# Test_Jig_BMP2.net
KiCad netlist of a schematic drawn in Altium Designer
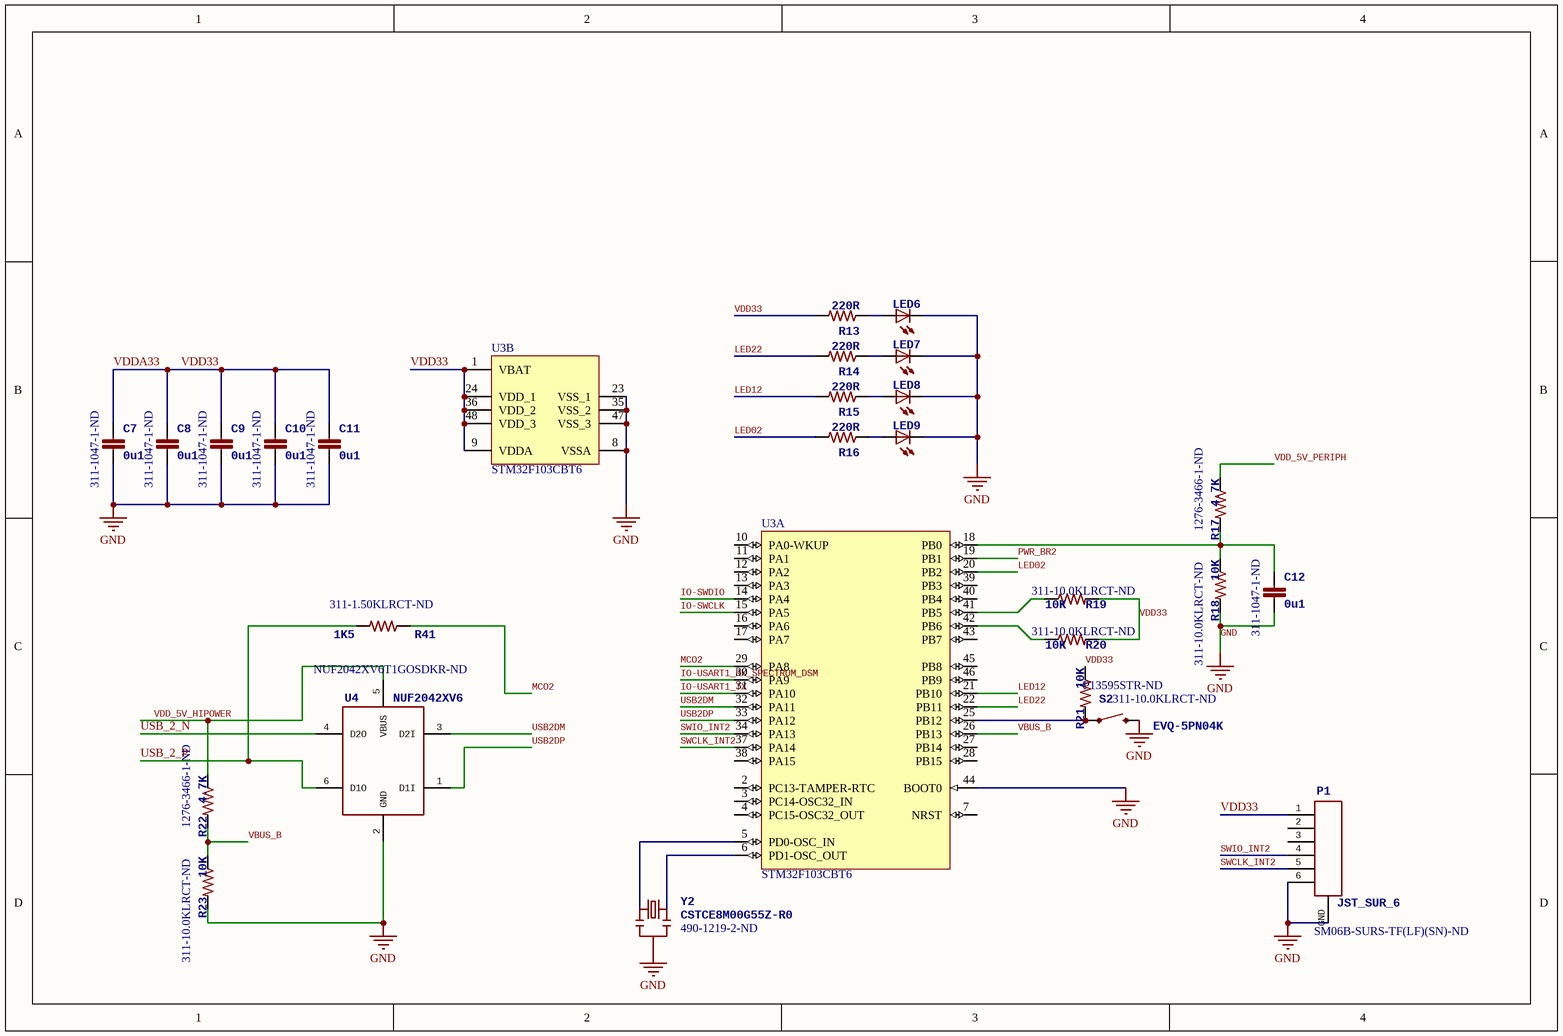
[diagram p0: Test_Jig_BMP2.SchDoc]

(export (version "E")
  (design (tool "Eeschema 10.0.6"))
  (components
    (comp (ref "C7")
      (value "0u1")
      (footprint "0402-CAP")
      (description "CAP CER 0.1UF 16V Y5V 0402")
      (fields
        (field (name "PARTNO") "CC0402ZRY5V7BB104")
        (field (name "SUPPLIER PART NUMBER 1") "311-1047-1-ND")
        (field (name "3DR_PARTNO") "ECM0700")
      )
      (libsource (lib "pixhawk2") (part "CAP0402"))
    )
    (comp (ref "C8")
      (value "0u1")
      (footprint "0402-CAP")
      (description "CAP CER 0.1UF 16V Y5V 0402")
      (fields
        (field (name "PARTNO") "CC0402ZRY5V7BB104")
        (field (name "SUPPLIER PART NUMBER 1") "311-1047-1-ND")
        (field (name "3DR_PARTNO") "ECM0700")
      )
      (libsource (lib "pixhawk2") (part "CAP0402"))
    )
    (comp (ref "C9")
      (value "0u1")
      (footprint "0402-CAP")
      (description "CAP CER 0.1UF 16V Y5V 0402")
      (fields
        (field (name "PARTNO") "CC0402ZRY5V7BB104")
        (field (name "SUPPLIER PART NUMBER 1") "311-1047-1-ND")
        (field (name "3DR_PARTNO") "ECM0700")
      )
      (libsource (lib "pixhawk2") (part "CAP0402"))
    )
    (comp (ref "C10")
      (value "0u1")
      (footprint "0402-CAP")
      (description "CAP CER 0.1UF 16V Y5V 0402")
      (fields
        (field (name "PARTNO") "CC0402ZRY5V7BB104")
        (field (name "SUPPLIER PART NUMBER 1") "311-1047-1-ND")
        (field (name "3DR_PARTNO") "ECM0700")
      )
      (libsource (lib "pixhawk2") (part "CAP0402"))
    )
    (comp (ref "C11")
      (value "0u1")
      (footprint "0402-CAP")
      (description "CAP CER 0.1UF 16V Y5V 0402")
      (fields
        (field (name "PARTNO") "CC0402ZRY5V7BB104")
        (field (name "SUPPLIER PART NUMBER 1") "311-1047-1-ND")
        (field (name "3DR_PARTNO") "ECM0700")
      )
      (libsource (lib "pixhawk2") (part "CAP0402"))
    )
    (comp (ref "C12")
      (value "0u1")
      (footprint "0402-CAP")
      (description "CAP CER 0.1UF 16V Y5V 0402")
      (fields
        (field (name "PARTNO") "CC0402ZRY5V7BB104")
        (field (name "SUPPLIER PART NUMBER 1") "311-1047-1-ND")
        (field (name "3DR_PARTNO") "ECM0700")
      )
      (libsource (lib "pixhawk2") (part "CAP0402"))
    )
    (comp (ref "LED6")
      (value "LED0603_Green")
      (footprint "0603-LED-Blue")
      (description "LED GREEN ROUND CLEAR SMD")
      (fields (field (name "3DR_PARTNO") "ECM0494") (field (name "PARTNO") "APTD1608CGCK"))
      (libsource (lib "pixhawk2") (part "LED0603_Blue"))
    )
    (comp (ref "LED7")
      (value "LED0603_Green")
      (footprint "0603-LED-Blue")
      (description "LED GREEN ROUND CLEAR SMD")
      (fields (field (name "3DR_PARTNO") "ECM0494") (field (name "PARTNO") "APTD1608CGCK"))
      (libsource (lib "pixhawk2") (part "LED0603_Blue"))
    )
    (comp (ref "LED8")
      (value "LED0603_Green")
      (footprint "0603-LED-Blue")
      (description "LED GREEN ROUND CLEAR SMD")
      (fields (field (name "3DR_PARTNO") "ECM0494") (field (name "PARTNO") "APTD1608CGCK"))
      (libsource (lib "pixhawk2") (part "LED0603_Blue"))
    )
    (comp (ref "LED9")
      (value "LED0603_Green")
      (footprint "0603-LED-Blue")
      (description "LED GREEN ROUND CLEAR SMD")
      (fields (field (name "3DR_PARTNO") "ECM0494") (field (name "PARTNO") "APTD1608CGCK"))
      (libsource (lib "pixhawk2") (part "LED0603_Blue"))
    )
    (comp (ref "P1")
      (value "JST_SUR_6")
      (footprint "JST_SUR_H6")
      (description "Connector, Header, 6Pos, .8mm IDC, R/A, SMD, Tin")
      (fields
        (field (name "SUPPLIER PART NUMBER 1") "SM06B-SURS-TF(LF)(SN)-ND")
        (field (name "3DR_PARTNO") "PRT0442")
      )
      (libsource (lib "PCA_0005_FULL_CB_REV_A") (part "JST_SUR_6"))
    )
    (comp (ref "R13")
      (value "220R")
      (footprint "0402-RES")
      (description "RES 220 OHM 1/16W 1% 0402 SMD")
      (fields (field (name "PARTNO") "RC0402FR-07220RL") (field (name "3DR_PARTNO") "ECM0821"))
      (libsource (lib "pixhawk2") (part "RESISTOR0402-RES"))
    )
    (comp (ref "R14")
      (value "220R")
      (footprint "0402-RES")
      (description "RES 220 OHM 1/16W 1% 0402 SMD")
      (fields (field (name "PARTNO") "RC0402FR-07220RL") (field (name "3DR_PARTNO") "ECM0821"))
      (libsource (lib "pixhawk2") (part "RESISTOR0402-RES"))
    )
    (comp (ref "R15")
      (value "220R")
      (footprint "0402-RES")
      (description "RES 220 OHM 1/16W 1% 0402 SMD")
      (fields (field (name "PARTNO") "RC0402FR-07220RL") (field (name "3DR_PARTNO") "ECM0821"))
      (libsource (lib "pixhawk2") (part "RESISTOR0402-RES"))
    )
    (comp (ref "R16")
      (value "220R")
      (footprint "0402-RES")
      (description "RES 220 OHM 1/16W 1% 0402 SMD")
      (fields (field (name "PARTNO") "RC0402FR-07220RL") (field (name "3DR_PARTNO") "ECM0821"))
      (libsource (lib "pixhawk2") (part "RESISTOR0402-RES"))
    )
    (comp (ref "R17")
      (value "4.7K")
      (footprint "0402-RES")
      (description "RES 10K OHM 1/16W 1% 0402 SMD")
      (fields (field (name "PARTNO") "RC1005F472CS") (field (name "SUPPLIER PART NUMBER 1") "1276-3466-1-ND"))
      (libsource (lib "pixhawk2") (part "RESISTOR0402-RES"))
    )
    (comp (ref "R18")
      (value "10K")
      (footprint "0402-RES")
      (description "RES 10K OHM 1/16W 1% 0402 SMD")
      (fields
        (field (name "PARTNO") "RC0402FR-0710KL")
        (field (name "SUPPLIER PART NUMBER 1") "311-10.0KLRCT-ND")
        (field (name "3DR_PARTNO") "ECM0800")
      )
      (libsource (lib "pixhawk2") (part "RESISTOR0402-RES"))
    )
    (comp (ref "R19")
      (value "10K")
      (footprint "0402-RES")
      (description "RES 10K OHM 1/16W 1% 0402 SMD")
      (fields
        (field (name "PARTNO") "RC0402FR-0710KL")
        (field (name "SUPPLIER PART NUMBER 1") "311-10.0KLRCT-ND")
        (field (name "3DR_PARTNO") "ECM0800")
      )
      (libsource (lib "pixhawk2") (part "RESISTOR0402-RES"))
    )
    (comp (ref "R20")
      (value "10K")
      (footprint "0402-RES")
      (description "RES 10K OHM 1/16W 1% 0402 SMD")
      (fields
        (field (name "PARTNO") "RC0402FR-0710KL")
        (field (name "SUPPLIER PART NUMBER 1") "311-10.0KLRCT-ND")
        (field (name "3DR_PARTNO") "ECM0800")
      )
      (libsource (lib "pixhawk2") (part "RESISTOR0402-RES"))
    )
    (comp (ref "R21")
      (value "10K")
      (footprint "0402-RES")
      (description "RES 10K OHM 1/16W 1% 0402 SMD")
      (fields
        (field (name "PARTNO") "RC0402FR-0710KL")
        (field (name "SUPPLIER PART NUMBER 1") "311-10.0KLRCT-ND")
        (field (name "3DR_PARTNO") "ECM0800")
      )
      (libsource (lib "pixhawk2") (part "RESISTOR0402-RES"))
    )
    (comp (ref "R22")
      (value "4.7K")
      (footprint "0402-RES")
      (description "RES 10K OHM 1/16W 1% 0402 SMD")
      (fields (field (name "PARTNO") "RC1005F472CS") (field (name "SUPPLIER PART NUMBER 1") "1276-3466-1-ND"))
      (libsource (lib "pixhawk2") (part "RESISTOR0402-RES"))
    )
    (comp (ref "R23")
      (value "10K")
      (footprint "0402-RES")
      (description "RES 10K OHM 1/16W 1% 0402 SMD")
      (fields
        (field (name "PARTNO") "RC0402FR-0710KL")
        (field (name "SUPPLIER PART NUMBER 1") "311-10.0KLRCT-ND")
        (field (name "3DR_PARTNO") "ECM0800")
      )
      (libsource (lib "pixhawk2") (part "RESISTOR0402-RES"))
    )
    (comp (ref "R41")
      (value "1K5")
      (footprint "0402-RES")
      (description "RES 1.5K OHM 1/16W 1% 0402 SMD")
      (fields
        (field (name "PARTNO") "RC0402FR-071K5L")
        (field (name "SUPPLIER PART NUMBER 1") "311-1.50KLRCT-ND")
        (field (name "3DR_PARTNO") "ECM0803")
      )
      (libsource (lib "pixhawk2") (part "RESISTOR0402-RES"))
    )
    (comp (ref "S2")
      (value "EVQ-5PN04K")
      (footprint "TACTILE-SWITCH-1101NE")
      (fields (field (name "SUPPLIER PART NUMBER 1") "P13595STR-ND"))
      (libsource (lib "pixhawk2") (part "SWITCH-MOMENTARY-2-SMD-1101NE"))
    )
    (comp (ref "U3")
      (value "STM32F103CBT6")
      (footprint "STM-LQFP48_N")
      (libsource (lib "STMicroelectronics STM32 F1") (part "STM32F103CBT6"))
    )
    (comp (ref "U4")
      (value "NUF2042XV6")
      (footprint "SOT563-6")
      (description "IC FILTER USB ESD PROTECT SOT363")
      (fields
        (field (name "PARTNO") "NUF2042XV6T1G")
        (field (name "SUPPLIER PART NUMBER 1") "NUF2042XV6T1GOSDKR-ND")
        (field (name "3DR_PARTNO") "ECM0836")
      )
      (libsource (lib "pixhawk2") (part "NUF2042XV6"))
    )
    (comp (ref "Y2")
      (value "CSTCE8M00G55Z-R0")
      (footprint "RESONATOR-SMD")
      (fields (field (name "SUPPLIER PART NUMBER 1") "490-1219-2-ND"))
      (libsource (lib "SparkFun") (part "RESONATORSMD"))
    )
  )
  (nets
    (net (code "1") (name "/IO-SWCLK") (class "Default")
      (node (ref "U3") (pin "15") (pinfunction "PA5_15") (pintype "bidirectional"))
    )
    (net (code "2") (name "/IO-SWDIO") (class "Default")
      (node (ref "U3") (pin "14") (pinfunction "PA4_14") (pintype "bidirectional"))
    )
    (net (code "3") (name "/IO-USART1_RX_SPECTRUM_DSM") (class "Default")
      (node (ref "U3") (pin "30") (pinfunction "PA9_30") (pintype "bidirectional"))
    )
    (net (code "4") (name "/IO-USART1_TX") (class "Default")
      (node (ref "U3") (pin "31") (pinfunction "PA10_31") (pintype "bidirectional"))
    )
    (net (code "5") (name "/LED02") (class "Default")
      (node (ref "R16") (pin "P$2") (pinfunction "2_P$2") (pintype "passive"))
      (node (ref "U3") (pin "20") (pinfunction "PB2_20") (pintype "bidirectional"))
    )
    (net (code "6") (name "/LED12") (class "Default")
      (node (ref "R15") (pin "P$2") (pinfunction "2_P$2") (pintype "passive"))
      (node (ref "U3") (pin "21") (pinfunction "PB10_21") (pintype "bidirectional"))
    )
    (net (code "7") (name "/LED22") (class "Default")
      (node (ref "R14") (pin "P$2") (pinfunction "2_P$2") (pintype "passive"))
      (node (ref "U3") (pin "22") (pinfunction "PB11_22") (pintype "bidirectional"))
    )
    (net (code "8") (name "/MCO2") (class "Default")
      (node (ref "R41") (pin "P$1") (pinfunction "1_P$1") (pintype "passive"))
      (node (ref "U3") (pin "29") (pinfunction "PA8_29") (pintype "bidirectional"))
    )
    (net (code "9") (name "/PWR_BR2") (class "Default")
      (node (ref "U3") (pin "19") (pinfunction "PB1_19") (pintype "bidirectional"))
    )
    (net (code "10") (name "/SWCLK_INT2") (class "Default")
      (node (ref "P1") (pin "5") (pinfunction "5_5") (pintype "passive"))
      (node (ref "U3") (pin "37") (pinfunction "PA14_37") (pintype "bidirectional"))
    )
    (net (code "11") (name "/SWIO_INT2") (class "Default")
      (node (ref "P1") (pin "4") (pinfunction "4_4") (pintype "passive"))
      (node (ref "U3") (pin "34") (pinfunction "PA13_34") (pintype "bidirectional"))
    )
    (net (code "12") (name "/USB2DM") (class "Default")
      (node (ref "U3") (pin "32") (pinfunction "PA11_32") (pintype "bidirectional"))
      (node (ref "U4") (pin "3") (pinfunction "D2I_3") (pintype "passive"))
    )
    (net (code "13") (name "/USB2DP") (class "Default")
      (node (ref "U3") (pin "33") (pinfunction "PA12_33") (pintype "bidirectional"))
      (node (ref "U4") (pin "1") (pinfunction "D1I_1") (pintype "passive"))
    )
    (net (code "14") (name "/USB_2_N") (class "Default")
      (node (ref "U4") (pin "4") (pinfunction "D2O_4") (pintype "passive"))
    )
    (net (code "15") (name "/USB_2_P") (class "Default")
      (node (ref "R41") (pin "P$2") (pinfunction "2_P$2") (pintype "passive"))
      (node (ref "U4") (pin "6") (pinfunction "D1O_6") (pintype "passive"))
    )
    (net (code "16") (name "/VBUS_B") (class "Default")
      (node (ref "R22") (pin "P$2") (pinfunction "2_P$2") (pintype "passive"))
      (node (ref "R23") (pin "P$1") (pinfunction "1_P$1") (pintype "passive"))
      (node (ref "U3") (pin "26") (pinfunction "PB13_26") (pintype "bidirectional"))
    )
    (net (code "17") (name "/VDD33") (class "Default")
      (node (ref "C10") (pin "P$1") (pinfunction "1_P$1") (pintype "passive"))
      (node (ref "C11") (pin "P$1") (pinfunction "1_P$1") (pintype "passive"))
      (node (ref "C7") (pin "P$1") (pinfunction "1_P$1") (pintype "passive"))
      (node (ref "C8") (pin "P$1") (pinfunction "1_P$1") (pintype "passive"))
      (node (ref "C9") (pin "P$1") (pinfunction "1_P$1") (pintype "passive"))
      (node (ref "P1") (pin "1") (pinfunction "1_1") (pintype "passive"))
      (node (ref "R13") (pin "P$2") (pinfunction "2_P$2") (pintype "passive"))
      (node (ref "R19") (pin "P$2") (pinfunction "2_P$2") (pintype "passive"))
      (node (ref "R20") (pin "P$2") (pinfunction "2_P$2") (pintype "passive"))
      (node (ref "R21") (pin "P$1") (pinfunction "1_P$1") (pintype "passive"))
      (node (ref "U3") (pin "1") (pinfunction "VBAT_1") (pintype "power_in"))
      (node (ref "U3") (pin "24") (pinfunction "VDD_1_24") (pintype "power_in"))
      (node (ref "U3") (pin "36") (pinfunction "VDD_2_36") (pintype "power_in"))
      (node (ref "U3") (pin "48") (pinfunction "VDD_3_48") (pintype "power_in"))
      (node (ref "U3") (pin "9") (pinfunction "VDDA_9") (pintype "power_in"))
    )
    (net (code "18") (name "/VDD_5V_HIPOWER") (class "Default")
      (node (ref "R22") (pin "P$1") (pinfunction "1_P$1") (pintype "passive"))
      (node (ref "U4") (pin "5") (pinfunction "VBUS_5") (pintype "passive"))
    )
    (net (code "19") (name "/VDD_5V_PERIPH") (class "Default")
      (node (ref "R17") (pin "P$1") (pinfunction "1_P$1") (pintype "passive"))
    )
    (net (code "20") (name "GND") (class "Default")
      (node (ref "C10") (pin "P$2") (pinfunction "2_P$2") (pintype "passive"))
      (node (ref "C11") (pin "P$2") (pinfunction "2_P$2") (pintype "passive"))
      (node (ref "C12") (pin "P$2") (pinfunction "2_P$2") (pintype "passive"))
      (node (ref "C7") (pin "P$2") (pinfunction "2_P$2") (pintype "passive"))
      (node (ref "C8") (pin "P$2") (pinfunction "2_P$2") (pintype "passive"))
      (node (ref "C9") (pin "P$2") (pinfunction "2_P$2") (pintype "passive"))
      (node (ref "LED6") (pin "C") (pinfunction "C_C") (pintype "passive"))
      (node (ref "LED7") (pin "C") (pinfunction "C_C") (pintype "passive"))
      (node (ref "LED8") (pin "C") (pinfunction "C_C") (pintype "passive"))
      (node (ref "LED9") (pin "C") (pinfunction "C_C") (pintype "passive"))
      (node (ref "P1") (pin "6") (pinfunction "6_6") (pintype "passive"))
      (node (ref "P1") (pin "GND") (pinfunction "GND_GND") (pintype "passive"))
      (node (ref "R18") (pin "P$2") (pinfunction "2_P$2") (pintype "passive"))
      (node (ref "R23") (pin "P$2") (pinfunction "2_P$2") (pintype "passive"))
      (node (ref "S2") (pin "2") (pinfunction "2_2") (pintype "passive"))
      (node (ref "U3") (pin "23") (pinfunction "VSS_1_23") (pintype "power_in"))
      (node (ref "U3") (pin "35") (pinfunction "VSS_2_35") (pintype "power_in"))
      (node (ref "U3") (pin "44") (pinfunction "BOOT0_44") (pintype "input"))
      (node (ref "U3") (pin "47") (pinfunction "VSS_3_47") (pintype "power_in"))
      (node (ref "U3") (pin "8") (pinfunction "VSSA_8") (pintype "power_in"))
      (node (ref "U4") (pin "2") (pinfunction "GND_2") (pintype "passive"))
      (node (ref "Y2") (pin "2") (pinfunction "2_2") (pintype "passive"))
    )
    (net (code "21") (name "Net-(C12-1)") (class "Default")
      (node (ref "C12") (pin "P$1") (pinfunction "1_P$1") (pintype "passive"))
      (node (ref "R17") (pin "P$2") (pinfunction "2_P$2") (pintype "passive"))
      (node (ref "R18") (pin "P$1") (pinfunction "1_P$1") (pintype "passive"))
      (node (ref "U3") (pin "18") (pinfunction "PB0_18") (pintype "bidirectional"))
    )
    (net (code "22") (name "Net-(R13-1)") (class "Default")
      (node (ref "LED6") (pin "A") (pinfunction "A_A") (pintype "passive"))
      (node (ref "R13") (pin "P$1") (pinfunction "1_P$1") (pintype "passive"))
    )
    (net (code "23") (name "Net-(R14-1)") (class "Default")
      (node (ref "LED7") (pin "A") (pinfunction "A_A") (pintype "passive"))
      (node (ref "R14") (pin "P$1") (pinfunction "1_P$1") (pintype "passive"))
    )
    (net (code "24") (name "Net-(R15-1)") (class "Default")
      (node (ref "LED8") (pin "A") (pinfunction "A_A") (pintype "passive"))
      (node (ref "R15") (pin "P$1") (pinfunction "1_P$1") (pintype "passive"))
    )
    (net (code "25") (name "Net-(R16-1)") (class "Default")
      (node (ref "LED9") (pin "A") (pinfunction "A_A") (pintype "passive"))
      (node (ref "R16") (pin "P$1") (pinfunction "1_P$1") (pintype "passive"))
    )
    (net (code "26") (name "Net-(R19-1)") (class "Default")
      (node (ref "R19") (pin "P$1") (pinfunction "1_P$1") (pintype "passive"))
      (node (ref "U3") (pin "41") (pinfunction "PB5_41") (pintype "bidirectional"))
    )
    (net (code "27") (name "Net-(R20-1)") (class "Default")
      (node (ref "R20") (pin "P$1") (pinfunction "1_P$1") (pintype "passive"))
      (node (ref "U3") (pin "42") (pinfunction "PB6_42") (pintype "bidirectional"))
    )
    (net (code "28") (name "Net-(R21-2)") (class "Default")
      (node (ref "R21") (pin "P$2") (pinfunction "2_P$2") (pintype "passive"))
      (node (ref "S2") (pin "1") (pinfunction "1_1") (pintype "passive"))
      (node (ref "U3") (pin "25") (pinfunction "PB12_25") (pintype "bidirectional"))
    )
    (net (code "29") (name "Net-(U3A-PD0-OSC_IN)") (class "Default")
      (node (ref "U3") (pin "5") (pinfunction "PD0-OSC_IN_5") (pintype "bidirectional"))
      (node (ref "Y2") (pin "1") (pinfunction "1_1") (pintype "passive"))
    )
    (net (code "30") (name "Net-(U3A-PD1-OSC_OUT)") (class "Default")
      (node (ref "U3") (pin "6") (pinfunction "PD1-OSC_OUT_6") (pintype "bidirectional"))
      (node (ref "Y2") (pin "3") (pinfunction "3_3") (pintype "passive"))
    )
    (net (code "31") (name "unconnected-(P1-Pad2)") (class "Default")
      (node (ref "P1") (pin "2") (pinfunction "2_2") (pintype "passive"))
    )
    (net (code "32") (name "unconnected-(P1-Pad3)") (class "Default")
      (node (ref "P1") (pin "3") (pinfunction "3_3") (pintype "passive"))
    )
    (net (code "33") (name "unconnected-(U3A-NRST-Pad7)") (class "Default")
      (node (ref "U3") (pin "7") (pinfunction "NRST_7") (pintype "bidirectional"))
    )
    (net (code "34") (name "unconnected-(U3A-PA0-WKUP-Pad10)") (class "Default")
      (node (ref "U3") (pin "10") (pinfunction "PA0-WKUP_10") (pintype "bidirectional"))
    )
    (net (code "35") (name "unconnected-(U3A-PA1-Pad11)") (class "Default")
      (node (ref "U3") (pin "11") (pinfunction "PA1_11") (pintype "bidirectional"))
    )
    (net (code "36") (name "unconnected-(U3A-PA2-Pad12)") (class "Default")
      (node (ref "U3") (pin "12") (pinfunction "PA2_12") (pintype "bidirectional"))
    )
    (net (code "37") (name "unconnected-(U3A-PA3-Pad13)") (class "Default")
      (node (ref "U3") (pin "13") (pinfunction "PA3_13") (pintype "bidirectional"))
    )
    (net (code "38") (name "unconnected-(U3A-PA6-Pad16)") (class "Default")
      (node (ref "U3") (pin "16") (pinfunction "PA6_16") (pintype "bidirectional"))
    )
    (net (code "39") (name "unconnected-(U3A-PA7-Pad17)") (class "Default")
      (node (ref "U3") (pin "17") (pinfunction "PA7_17") (pintype "bidirectional"))
    )
    (net (code "40") (name "unconnected-(U3A-PA15-Pad38)") (class "Default")
      (node (ref "U3") (pin "38") (pinfunction "PA15_38") (pintype "bidirectional"))
    )
    (net (code "41") (name "unconnected-(U3A-PB3-Pad39)") (class "Default")
      (node (ref "U3") (pin "39") (pinfunction "PB3_39") (pintype "bidirectional"))
    )
    (net (code "42") (name "unconnected-(U3A-PB4-Pad40)") (class "Default")
      (node (ref "U3") (pin "40") (pinfunction "PB4_40") (pintype "bidirectional"))
    )
    (net (code "43") (name "unconnected-(U3A-PB7-Pad43)") (class "Default")
      (node (ref "U3") (pin "43") (pinfunction "PB7_43") (pintype "bidirectional"))
    )
    (net (code "44") (name "unconnected-(U3A-PB8-Pad45)") (class "Default")
      (node (ref "U3") (pin "45") (pinfunction "PB8_45") (pintype "bidirectional"))
    )
    (net (code "45") (name "unconnected-(U3A-PB9-Pad46)") (class "Default")
      (node (ref "U3") (pin "46") (pinfunction "PB9_46") (pintype "bidirectional"))
    )
    (net (code "46") (name "unconnected-(U3A-PB14-Pad27)") (class "Default")
      (node (ref "U3") (pin "27") (pinfunction "PB14_27") (pintype "bidirectional"))
    )
    (net (code "47") (name "unconnected-(U3A-PB15-Pad28)") (class "Default")
      (node (ref "U3") (pin "28") (pinfunction "PB15_28") (pintype "bidirectional"))
    )
    (net (code "48") (name "unconnected-(U3A-PC13-TAMPER-RTC-Pad2)") (class "Default")
      (node (ref "U3") (pin "2") (pinfunction "PC13-TAMPER-RTC_2") (pintype "bidirectional"))
    )
    (net (code "49") (name "unconnected-(U3A-PC14-OSC32_IN-Pad3)") (class "Default")
      (node (ref "U3") (pin "3") (pinfunction "PC14-OSC32_IN_3") (pintype "bidirectional"))
    )
    (net (code "50") (name "unconnected-(U3A-PC15-OSC32_OUT-Pad4)") (class "Default")
      (node (ref "U3") (pin "4") (pinfunction "PC15-OSC32_OUT_4") (pintype "bidirectional"))
    )
  )
)
